# System_Power.net
KiCad netlist of a schematic drawn in Altium Designer
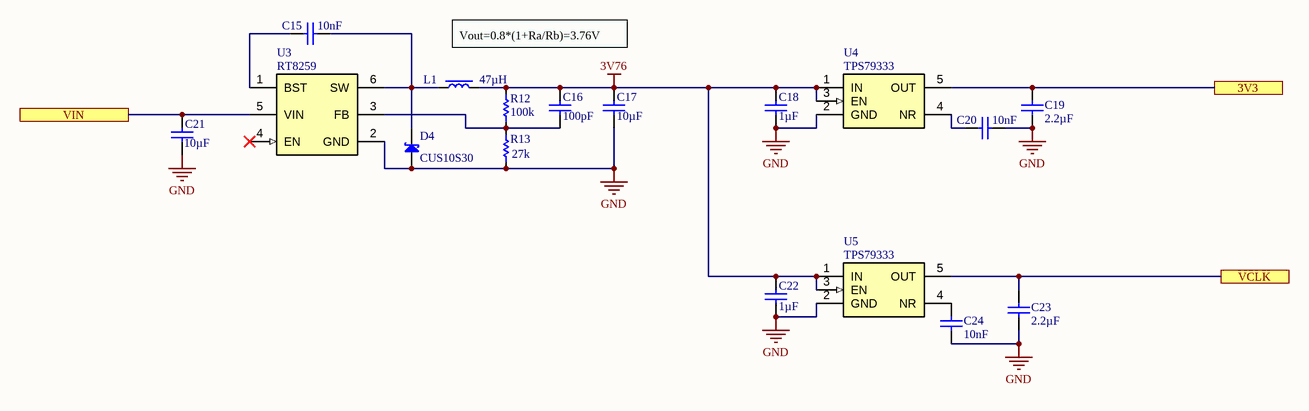
[diagram p0: System Power.SchDoc]

(export (version "E")
  (design (tool "Eeschema 10.0.6"))
  (components
    (comp (ref "C15")
      (value "10nF")
      (footprint "CAP_CHIP_0603")
      (description "0603 Multilayer Ceramic Capacitors MLCC")
      (fields (field (name "PARTNUMBER") "0603B103K500NT") (field (name "TOLERANCE") "10%"))
      (libsource (lib "Sainsbury Wellcome Centre") (part "Cap"))
    )
    (comp (ref "C16")
      (value "100pF")
      (footprint "CAP_CHIP_0603")
      (description "0603 Multilayer Ceramic Capacitors MLCC")
      (fields (field (name "TOLERANCE") "5%") (field (name "PARTNUMBER") "CL10C101JB8NNNC"))
      (libsource (lib "Sainsbury Wellcome Centre") (part "Cap"))
    )
    (comp (ref "C17")
      (value "10µF")
      (footprint "CAP_CHIP_0603")
      (fields
        (field (name "PARTNUMBER") "GRM188R6YA106MA73D")
        (field (name "TOLERANCE") "20%")
        (field (name "Comment") "C0603-10uF-35V")
      )
      (libsource (lib "Sainsbury Wellcome Centre") (part "Cap"))
    )
    (comp (ref "C18")
      (value "1µF")
      (footprint "CAP_CHIP_0603")
      (description "0603 Multilayer Ceramic Capacitors MLCC")
      (fields (field (name "PARTNUMBER") "CL10A105KB8NNNC") (field (name "TOLERANCE") "10%"))
      (libsource (lib "Sainsbury Wellcome Centre") (part "Cap"))
    )
    (comp (ref "C19")
      (value "2.2µF")
      (footprint "CAP_CHIP_0603")
      (description "0603 Multilayer Ceramic Capacitors MLCC")
      (fields (field (name "PARTNUMBER") "GRM188R61H225KE11D") (field (name "TOLERANCE") "10%"))
      (libsource (lib "Sainsbury Wellcome Centre") (part "Cap"))
    )
    (comp (ref "C20")
      (value "10nF")
      (footprint "CAP_CHIP_0603")
      (description "0603 Multilayer Ceramic Capacitors MLCC")
      (fields (field (name "TOLERANCE") "10%") (field (name "PARTNUMBER") "CL10B103KC84PEL"))
      (libsource (lib "Sainsbury Wellcome Centre") (part "Cap"))
    )
    (comp (ref "C21")
      (value "10µF")
      (footprint "CAP_CHIP_0603")
      (fields
        (field (name "PARTNUMBER") "GRM188R6YA106MA73D")
        (field (name "TOLERANCE") "20%")
        (field (name "Comment") "C0603-10uF-35V")
      )
      (libsource (lib "Sainsbury Wellcome Centre") (part "Cap"))
    )
    (comp (ref "C22")
      (value "1µF")
      (footprint "CAP_CHIP_0603")
      (description "0603 Multilayer Ceramic Capacitors MLCC")
      (fields (field (name "PARTNUMBER") "CL10A105KB8NNNC") (field (name "TOLERANCE") "10%"))
      (libsource (lib "Sainsbury Wellcome Centre") (part "Cap"))
    )
    (comp (ref "C23")
      (value "2.2µF")
      (footprint "CAP_CHIP_0603")
      (description "0603 Multilayer Ceramic Capacitors MLCC")
      (fields (field (name "PARTNUMBER") "GRM188R61H225KE11D") (field (name "TOLERANCE") "10%"))
      (libsource (lib "Sainsbury Wellcome Centre") (part "Cap"))
    )
    (comp (ref "C24")
      (value "10nF")
      (footprint "CAP_CHIP_0603")
      (description "0603 Multilayer Ceramic Capacitors MLCC")
      (fields (field (name "TOLERANCE") "10%") (field (name "PARTNUMBER") "CL10B103KC84PEL"))
      (libsource (lib "Sainsbury Wellcome Centre") (part "Cap"))
    )
    (comp (ref "D4")
      (value "CUS10S30")
      (footprint "SOD323")
      (description "Rectifier Diode, Schottky, 1 Phase, 1 Element, 1A, 30V V(RRM), Silicon")
      (fields (field (name "PARTNUMBER") "CUS10S30,H3F"))
      (libsource (lib "Sainsbury Wellcome Centre") (part "Diode-Schottky"))
    )
    (comp (ref "L1")
      (value "47µH")
      (footprint "IND_PWR_1210")
      (description "Inductor Power Chip Shielded Wirewound 47uH 20% 1MHz Ferrite 0.5A 0.9Ohm DCR 1210 Automotive T/R")
      (fields (field (name "TOLERANCE") "20%") (field (name "PARTNUMBER") "LQW32FT470M0HL"))
      (libsource (lib "Sainsbury Wellcome Centre") (part "Inductor"))
    )
    (comp (ref "R12")
      (value "100k")
      (footprint "RES_CHIP_0603")
      (description "100mW Thick Film Resistors 75V ±100ppm/℃ ±1% 0603 Chip Resistor")
      (fields (field (name "PARTNUMBER") "0603WAF1003T5E") (field (name "TOLERANCE") "1%"))
      (libsource (lib "Sainsbury Wellcome Centre") (part "Res"))
    )
    (comp (ref "R13")
      (value "27k")
      (footprint "RES_CHIP_0603")
      (description "100mW Thick Film Resistors 75V ±100ppm/℃ ±1% 0603 Chip Resistor")
      (fields (field (name "TOLERANCE") "1%") (field (name "PARTNUMBER") "0603WAF2702T5E"))
      (libsource (lib "Sainsbury Wellcome Centre") (part "Res"))
    )
    (comp (ref "U3")
      (value "RT8259")
      (footprint "SOT23-6")
      (description "Step-down type Adjustable 800mV~15V 1.2A 4.5V~24V Switching Regulator/Controller")
      (fields (field (name "PARTNUMBER") "RT8259GJ6"))
      (libsource (lib "Sainsbury Wellcome Centre") (part "RT8259"))
    )
    (comp (ref "U4")
      (value "TPS79333")
      (footprint "SOT23-5")
      (description "LDO Regulator Pos 3.3V 0.2A 5-Pin SOT-23-5 200mA")
      (fields (field (name "PARTNUMBER") "TPS79333DBVR"))
      (libsource (lib "Sainsbury Wellcome Centre") (part "LDO-5P-NR"))
    )
    (comp (ref "U5")
      (value "TPS79333")
      (footprint "SOT23-5")
      (description "LDO Regulator Pos 3.3V 0.2A 5-Pin SOT-23-5 200mA")
      (fields (field (name "PARTNUMBER") "TPS79333DBVR"))
      (libsource (lib "Sainsbury Wellcome Centre") (part "LDO-5P-NR"))
    )
  )
  (nets
    (net (code "1") (name "/3V3") (class "Default")
      (node (ref "C19") (pin "2") (pinfunction "2_2") (pintype "passive"))
      (node (ref "U4") (pin "5") (pinfunction "OUT_5") (pintype "power_in"))
    )
    (net (code "2") (name "/VCLK") (class "Default")
      (node (ref "C23") (pin "2") (pinfunction "2_2") (pintype "passive"))
      (node (ref "U5") (pin "5") (pinfunction "OUT_5") (pintype "power_in"))
    )
    (net (code "3") (name "/VIN") (class "Default")
      (node (ref "C21") (pin "2") (pinfunction "2_2") (pintype "passive"))
      (node (ref "U3") (pin "5") (pinfunction "VIN_5") (pintype "power_in"))
    )
    (net (code "4") (name "3V76") (class "Default")
      (node (ref "C16") (pin "2") (pinfunction "2_2") (pintype "passive"))
      (node (ref "C17") (pin "2") (pinfunction "2_2") (pintype "passive"))
      (node (ref "C18") (pin "2") (pinfunction "2_2") (pintype "passive"))
      (node (ref "C22") (pin "2") (pinfunction "2_2") (pintype "passive"))
      (node (ref "L1") (pin "2") (pinfunction "2_2") (pintype "passive"))
      (node (ref "R12") (pin "2") (pinfunction "2_2") (pintype "passive"))
      (node (ref "U4") (pin "1") (pinfunction "IN_1") (pintype "power_in"))
      (node (ref "U4") (pin "3") (pinfunction "EN_3") (pintype "input"))
      (node (ref "U5") (pin "1") (pinfunction "IN_1") (pintype "power_in"))
      (node (ref "U5") (pin "3") (pinfunction "EN_3") (pintype "input"))
    )
    (net (code "5") (name "GND") (class "Default")
      (node (ref "C17") (pin "1") (pinfunction "1_1") (pintype "passive"))
      (node (ref "C18") (pin "1") (pinfunction "1_1") (pintype "passive"))
      (node (ref "C19") (pin "1") (pinfunction "1_1") (pintype "passive"))
      (node (ref "C20") (pin "1") (pinfunction "1_1") (pintype "passive"))
      (node (ref "C21") (pin "1") (pinfunction "1_1") (pintype "passive"))
      (node (ref "C22") (pin "1") (pinfunction "1_1") (pintype "passive"))
      (node (ref "C23") (pin "1") (pinfunction "1_1") (pintype "passive"))
      (node (ref "C24") (pin "1") (pinfunction "1_1") (pintype "passive"))
      (node (ref "D4") (pin "2") (pinfunction "A_2") (pintype "passive"))
      (node (ref "R13") (pin "1") (pinfunction "1_1") (pintype "passive"))
      (node (ref "U3") (pin "2") (pinfunction "GND_2") (pintype "power_in"))
      (node (ref "U4") (pin "2") (pinfunction "GND_2") (pintype "power_in"))
      (node (ref "U5") (pin "2") (pinfunction "GND_2") (pintype "power_in"))
    )
    (net (code "6") (name "Net-(D4-C)") (class "Default")
      (node (ref "C15") (pin "1") (pinfunction "1_1") (pintype "passive"))
      (node (ref "D4") (pin "1") (pinfunction "C_1") (pintype "passive"))
      (node (ref "L1") (pin "1") (pinfunction "1_1") (pintype "passive"))
      (node (ref "U3") (pin "6") (pinfunction "SW_6") (pintype "passive"))
    )
    (net (code "7") (name "Net-(U3-BST)") (class "Default")
      (node (ref "C15") (pin "2") (pinfunction "2_2") (pintype "passive"))
      (node (ref "U3") (pin "1") (pinfunction "BST_1") (pintype "passive"))
    )
    (net (code "8") (name "Net-(U3-FB)") (class "Default")
      (node (ref "C16") (pin "1") (pinfunction "1_1") (pintype "passive"))
      (node (ref "R12") (pin "1") (pinfunction "1_1") (pintype "passive"))
      (node (ref "R13") (pin "2") (pinfunction "2_2") (pintype "passive"))
      (node (ref "U3") (pin "3") (pinfunction "FB_3") (pintype "passive"))
    )
    (net (code "9") (name "Net-(U4-NR)") (class "Default")
      (node (ref "C20") (pin "2") (pinfunction "2_2") (pintype "passive"))
      (node (ref "U4") (pin "4") (pinfunction "NR_4") (pintype "passive"))
    )
    (net (code "10") (name "Net-(U5-NR)") (class "Default")
      (node (ref "C24") (pin "2") (pinfunction "2_2") (pintype "passive"))
      (node (ref "U5") (pin "4") (pinfunction "NR_4") (pintype "passive"))
    )
    (net (code "11") (name "unconnected-(U3-EN-Pad4)") (class "Default")
      (node (ref "U3") (pin "4") (pinfunction "EN_4") (pintype "input+no_connect"))
    )
  )
)
